# project_Sheet.net
KiCad netlist of a schematic drawn in Altium Designer
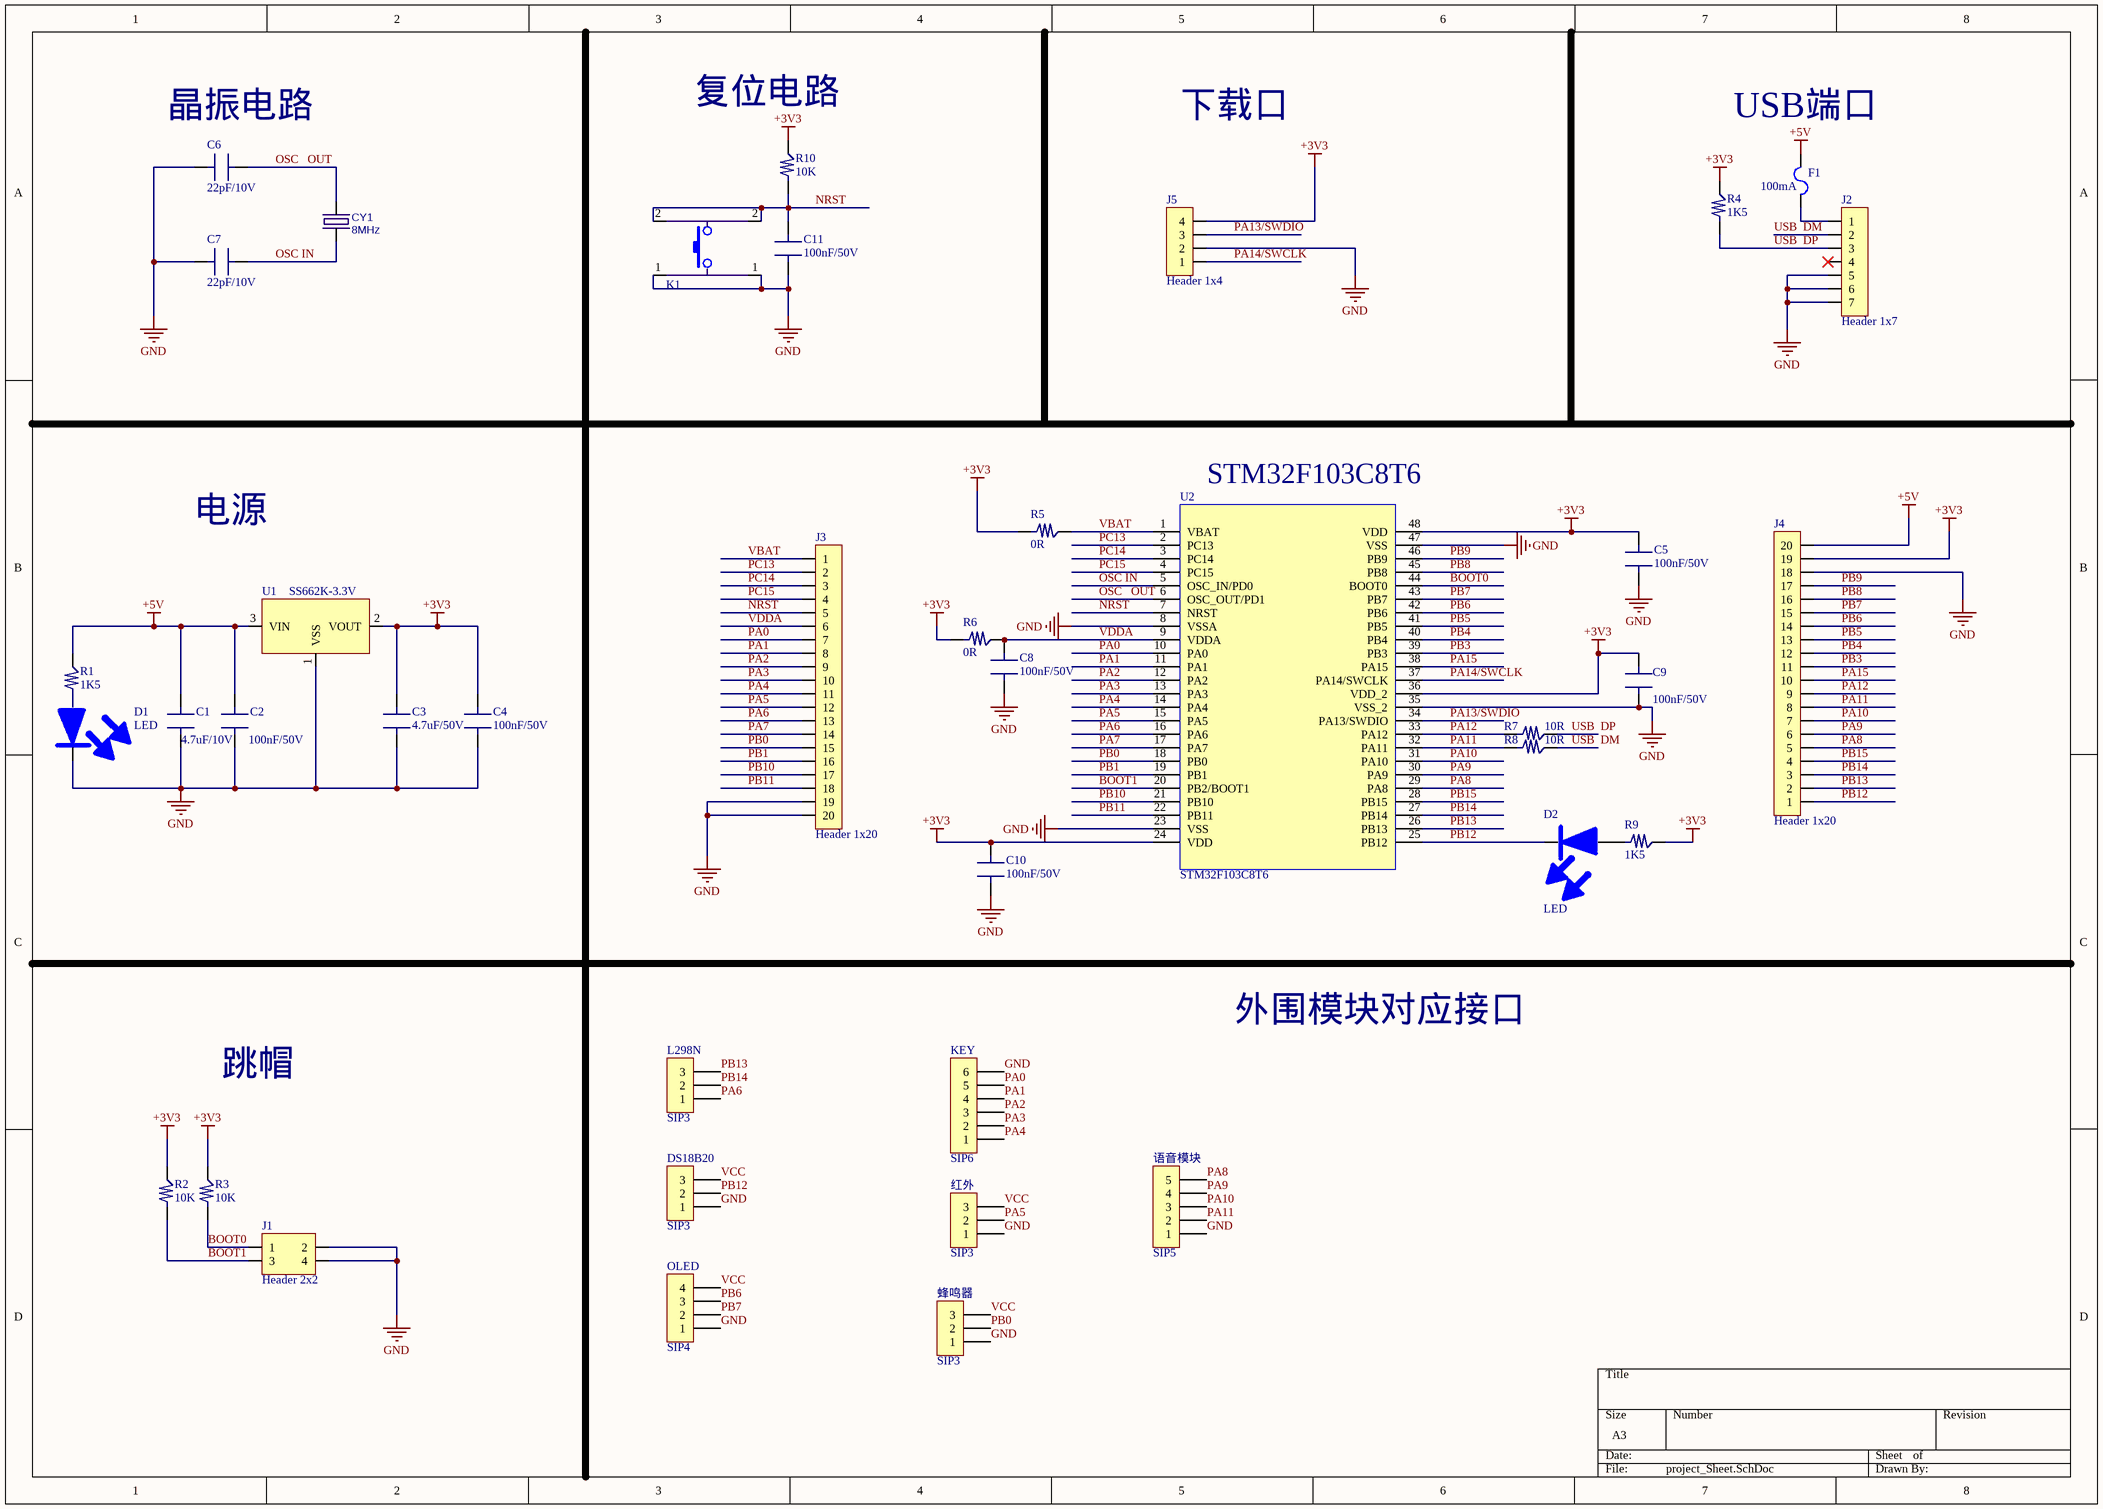
[diagram p0: project_Sheet.SchDoc]

(export (version "E")
  (design (tool "Eeschema 10.0.6"))
  (components
    (comp (ref "C1") (value "4.7uF/10V") (footprint "0603CC") (libsource (lib "F1A") (part "CAP")))
    (comp (ref "C2") (value "100nF/50V") (footprint "0603CC") (libsource (lib "F1A") (part "CAP")))
    (comp (ref "C3") (value "4.7uF/50V") (footprint "0805CC") (libsource (lib "F1A") (part "CAP")))
    (comp (ref "C4") (value "100nF/50V") (footprint "0805CC") (libsource (lib "F1A") (part "CAP")))
    (comp (ref "C5") (value "100nF/50V") (footprint "0603CC") (libsource (lib "F1A") (part "CAP")))
    (comp (ref "C6") (value "22pF/10V") (footprint "0603CC") (libsource (lib "F1A") (part "CAP")))
    (comp (ref "C7") (value "22pF/10V") (footprint "0603CC") (libsource (lib "F1A") (part "CAP")))
    (comp (ref "C8") (value "100nF/50V") (footprint "0603CC") (libsource (lib "F1A") (part "CAP")))
    (comp (ref "C9") (value "100nF/50V") (footprint "0603CC") (libsource (lib "F1A") (part "CAP")))
    (comp (ref "C10") (value "100nF/50V") (footprint "0603CC") (libsource (lib "F1A") (part "CAP")))
    (comp (ref "C11") (value "100nF/50V") (footprint "0603CC") (libsource (lib "F1A") (part "CAP")))
    (comp (ref "CY1")
      (value "8MHz")
      (footprint "HC-49S")
      (description "2pin晶振")
      (libsource (lib "F1A") (part "CY2P"))
    )
    (comp (ref "D1") (value "LED") (footprint "0603LED") (libsource (lib "F1A") (part "LED")))
    (comp (ref "D2") (value "LED") (footprint "0603LED") (libsource (lib "F1A") (part "LED")))
    (comp (ref "DS18B20")
      (value "SIP3")
      (footprint "SIP3-2.0")
      (description "jointbar")
      (libsource (lib "接口与插座") (part "SIP3"))
    )
    (comp (ref "F1")
      (value "100mA")
      (footprint "R0805")
      (description "保险丝")
      (libsource (lib "F1A") (part "FUSE"))
    )
    (comp (ref "J1")
      (value "Header 2x2")
      (footprint "HDR2X2")
      (description "双排连接器")
      (libsource (lib "F1A") (part "Header2*2"))
    )
    (comp (ref "J2")
      (value "Header 1x7")
      (footprint "PCBComponent_1")
      (description "单排连接器")
      (libsource (lib "F1A") (part "Header 1x7"))
    )
    (comp (ref "J3")
      (value "Header 1x20")
      (footprint "HDR1X20")
      (description "单排连接器")
      (libsource (lib "") (part "Header 1x20_1"))
    )
    (comp (ref "J4")
      (value "Header 1x20")
      (footprint "HDR1X20")
      (description "单排连接器")
      (libsource (lib "F1A") (part "Header 1x20"))
    )
    (comp (ref "J5")
      (value "Header 1x4")
      (footprint "HDR1X4")
      (description "单排连接器")
      (libsource (lib "F1A") (part "Header 1x4"))
    )
    (comp (ref "K1")
      (value "SW4P")
      (footprint "4.5*4.5*3.8")
      (description "4Pin轻触按键")
      (libsource (lib "F1A") (part "SW4P"))
    )
    (comp (ref "KEY")
      (value "SIP6")
      (footprint "SIP6-2.0")
      (description "jointbar")
      (libsource (lib "接口与插座") (part "SIP6"))
    )
    (comp (ref "L298N")
      (value "SIP3")
      (footprint "SIP3-2.0")
      (description "jointbar")
      (libsource (lib "接口与插座") (part "SIP3"))
    )
    (comp (ref "OLED")
      (value "SIP4")
      (footprint "SIP4-2.0")
      (description "jointbar")
      (libsource (lib "接口与插座") (part "SIP4"))
    )
    (comp (ref "R1")
      (value "1K5")
      (footprint "0603R")
      (description "分立电阻")
      (libsource (lib "F1A") (part "RES"))
    )
    (comp (ref "R2")
      (value "10K")
      (footprint "0603R")
      (description "分立电阻")
      (libsource (lib "F1A") (part "RES"))
    )
    (comp (ref "R3")
      (value "10K")
      (footprint "0603R")
      (description "分立电阻")
      (libsource (lib "F1A") (part "RES"))
    )
    (comp (ref "R4")
      (value "1K5")
      (footprint "0603R")
      (description "分立电阻")
      (libsource (lib "F1A") (part "RES"))
    )
    (comp (ref "R5")
      (value "0R")
      (footprint "0603R")
      (description "分立电阻")
      (libsource (lib "F1A") (part "RES"))
    )
    (comp (ref "R6")
      (value "0R")
      (footprint "0603R")
      (description "分立电阻")
      (libsource (lib "F1A") (part "RES"))
    )
    (comp (ref "R7")
      (value "10R")
      (footprint "0603R")
      (description "分立电阻")
      (libsource (lib "F1A") (part "RES"))
    )
    (comp (ref "R8")
      (value "10R")
      (footprint "0603R")
      (description "分立电阻")
      (libsource (lib "F1A") (part "RES"))
    )
    (comp (ref "R9")
      (value "1K5")
      (footprint "0603R")
      (description "分立电阻")
      (libsource (lib "F1A") (part "RES"))
    )
    (comp (ref "R10")
      (value "10K")
      (footprint "0603R")
      (description "分立电阻")
      (libsource (lib "F1A") (part "RES"))
    )
    (comp (ref "U1") (value "SS662K-3.3V") (footprint "SOT23-JX") (libsource (lib "F1A") (part "SS662K")))
    (comp (ref "U2")
      (value "STM32F103C8T6")
      (footprint "LQFP48")
      (description "STM32单片机")
      (libsource (lib "F1A") (part "STM32F103C8T6"))
    )
    (comp (ref "红外")
      (value "SIP3")
      (footprint "SIP3-2.0")
      (description "jointbar")
      (libsource (lib "接口与插座") (part "SIP3"))
    )
    (comp (ref "蜂鸣器")
      (value "SIP3")
      (footprint "SIP3-2.0")
      (description "jointbar")
      (libsource (lib "接口与插座") (part "SIP3"))
    )
    (comp (ref "语音模块")
      (value "SIP5")
      (footprint "SIP5-2.0")
      (description "jointbar")
      (libsource (lib "接口与插座") (part "SIP5"))
    )
  )
  (nets
    (net (code "1") (name "+3V3") (class "Default")
      (node (ref "C10") (pin "2") (pinfunction "2_2") (pintype "passive"))
      (node (ref "C3") (pin "2") (pinfunction "2_2") (pintype "passive"))
      (node (ref "C4") (pin "2") (pinfunction "2_2") (pintype "passive"))
      (node (ref "C5") (pin "2") (pinfunction "2_2") (pintype "passive"))
      (node (ref "C9") (pin "2") (pinfunction "2_2") (pintype "passive"))
      (node (ref "J4") (pin "19") (pinfunction "19_19") (pintype "passive"))
      (node (ref "J5") (pin "4") (pinfunction "4_4") (pintype "passive"))
      (node (ref "R10") (pin "2") (pinfunction "2_2") (pintype "passive"))
      (node (ref "R2") (pin "2") (pinfunction "2_2") (pintype "passive"))
      (node (ref "R3") (pin "2") (pinfunction "2_2") (pintype "passive"))
      (node (ref "R4") (pin "2") (pinfunction "2_2") (pintype "passive"))
      (node (ref "R5") (pin "1") (pinfunction "1_1") (pintype "passive"))
      (node (ref "R6") (pin "1") (pinfunction "1_1") (pintype "passive"))
      (node (ref "R9") (pin "2") (pinfunction "2_2") (pintype "passive"))
      (node (ref "U1") (pin "2") (pinfunction "VOUT_2") (pintype "passive"))
      (node (ref "U2") (pin "24") (pinfunction "VDD_24") (pintype "passive"))
      (node (ref "U2") (pin "36") (pinfunction "VDD_2_36") (pintype "passive"))
      (node (ref "U2") (pin "48") (pinfunction "VDD_48") (pintype "passive"))
    )
    (net (code "2") (name "+5V") (class "Default")
      (node (ref "C1") (pin "2") (pinfunction "2_2") (pintype "passive"))
      (node (ref "C2") (pin "2") (pinfunction "2_2") (pintype "passive"))
      (node (ref "F1") (pin "2") (pinfunction "2_2") (pintype "passive"))
      (node (ref "J4") (pin "20") (pinfunction "20_20") (pintype "passive"))
      (node (ref "R1") (pin "2") (pinfunction "2_2") (pintype "passive"))
      (node (ref "U1") (pin "3") (pinfunction "VIN_3") (pintype "passive"))
    )
    (net (code "3") (name "/BOOT0") (class "Default")
      (node (ref "J1") (pin "1") (pinfunction "1_1") (pintype "passive"))
      (node (ref "R3") (pin "1") (pinfunction "1_1") (pintype "passive"))
      (node (ref "U2") (pin "44") (pinfunction "BOOT0_44") (pintype "passive"))
    )
    (net (code "4") (name "/BOOT1") (class "Default")
      (node (ref "J1") (pin "3") (pinfunction "3_3") (pintype "passive"))
      (node (ref "R2") (pin "1") (pinfunction "1_1") (pintype "passive"))
      (node (ref "U2") (pin "20") (pinfunction "PB2/BOOT1_20") (pintype "passive"))
    )
    (net (code "5") (name "/NRST") (class "Default")
      (node (ref "C11") (pin "2") (pinfunction "2_2") (pintype "passive"))
      (node (ref "J3") (pin "5") (pinfunction "5_5") (pintype "passive"))
      (node (ref "K1") (pin "2") (pinfunction "3_2") (pintype "passive"))
      (node (ref "R10") (pin "1") (pinfunction "1_1") (pintype "passive"))
      (node (ref "U2") (pin "7") (pinfunction "NRST_7") (pintype "passive"))
    )
    (net (code "6") (name "/OSC   OUT") (class "Default")
      (node (ref "C6") (pin "2") (pinfunction "2_2") (pintype "passive"))
      (node (ref "CY1") (pin "2") (pinfunction "2_2") (pintype "passive"))
      (node (ref "U2") (pin "6") (pinfunction "OSC_OUT/PD1_6") (pintype "passive"))
    )
    (net (code "7") (name "/OSC IN") (class "Default")
      (node (ref "C7") (pin "2") (pinfunction "2_2") (pintype "passive"))
      (node (ref "CY1") (pin "1") (pinfunction "1_1") (pintype "passive"))
      (node (ref "U2") (pin "5") (pinfunction "OSC_IN/PD0_5") (pintype "passive"))
    )
    (net (code "8") (name "/PA0") (class "Default")
      (node (ref "J3") (pin "7") (pinfunction "7_7") (pintype "passive"))
      (node (ref "KEY") (pin "5") (pinfunction "5_5") (pintype "passive"))
      (node (ref "U2") (pin "10") (pinfunction "PA0_10") (pintype "passive"))
    )
    (net (code "9") (name "/PA1") (class "Default")
      (node (ref "J3") (pin "8") (pinfunction "8_8") (pintype "passive"))
      (node (ref "KEY") (pin "4") (pinfunction "4_4") (pintype "passive"))
      (node (ref "U2") (pin "11") (pinfunction "PA1_11") (pintype "passive"))
    )
    (net (code "10") (name "/PA2") (class "Default")
      (node (ref "J3") (pin "9") (pinfunction "9_9") (pintype "passive"))
      (node (ref "KEY") (pin "3") (pinfunction "3_3") (pintype "passive"))
      (node (ref "U2") (pin "12") (pinfunction "PA2_12") (pintype "passive"))
    )
    (net (code "11") (name "/PA3") (class "Default")
      (node (ref "J3") (pin "10") (pinfunction "10_10") (pintype "passive"))
      (node (ref "KEY") (pin "2") (pinfunction "2_2") (pintype "passive"))
      (node (ref "U2") (pin "13") (pinfunction "PA3_13") (pintype "passive"))
    )
    (net (code "12") (name "/PA4") (class "Default")
      (node (ref "J3") (pin "11") (pinfunction "11_11") (pintype "passive"))
      (node (ref "KEY") (pin "1") (pinfunction "1_1") (pintype "passive"))
      (node (ref "U2") (pin "14") (pinfunction "PA4_14") (pintype "passive"))
    )
    (net (code "13") (name "/PA5") (class "Default")
      (node (ref "J3") (pin "12") (pinfunction "12_12") (pintype "passive"))
      (node (ref "U2") (pin "15") (pinfunction "PA5_15") (pintype "passive"))
      (node (ref "红外") (pin "2") (pinfunction "2_2") (pintype "passive"))
    )
    (net (code "14") (name "/PA6") (class "Default")
      (node (ref "J3") (pin "13") (pinfunction "13_13") (pintype "passive"))
      (node (ref "L298N") (pin "1") (pinfunction "1_1") (pintype "passive"))
      (node (ref "U2") (pin "16") (pinfunction "PA6_16") (pintype "passive"))
    )
    (net (code "15") (name "/PA7") (class "Default")
      (node (ref "J3") (pin "14") (pinfunction "14_14") (pintype "passive"))
      (node (ref "U2") (pin "17") (pinfunction "PA7_17") (pintype "passive"))
    )
    (net (code "16") (name "/PA8") (class "Default")
      (node (ref "J4") (pin "5") (pinfunction "5_5") (pintype "passive"))
      (node (ref "U2") (pin "29") (pinfunction "PA8_29") (pintype "passive"))
      (node (ref "语音模块") (pin "5") (pinfunction "5_5") (pintype "passive"))
    )
    (net (code "17") (name "/PA9") (class "Default")
      (node (ref "J4") (pin "6") (pinfunction "6_6") (pintype "passive"))
      (node (ref "U2") (pin "30") (pinfunction "PA9_30") (pintype "passive"))
      (node (ref "语音模块") (pin "4") (pinfunction "4_4") (pintype "passive"))
    )
    (net (code "18") (name "/PA10") (class "Default")
      (node (ref "J4") (pin "7") (pinfunction "7_7") (pintype "passive"))
      (node (ref "U2") (pin "31") (pinfunction "PA10_31") (pintype "passive"))
      (node (ref "语音模块") (pin "3") (pinfunction "3_3") (pintype "passive"))
    )
    (net (code "19") (name "/PA11") (class "Default")
      (node (ref "J4") (pin "8") (pinfunction "8_8") (pintype "passive"))
      (node (ref "R8") (pin "1") (pinfunction "1_1") (pintype "passive"))
      (node (ref "U2") (pin "32") (pinfunction "PA11_32") (pintype "passive"))
      (node (ref "语音模块") (pin "2") (pinfunction "2_2") (pintype "passive"))
    )
    (net (code "20") (name "/PA12") (class "Default")
      (node (ref "J4") (pin "9") (pinfunction "9_9") (pintype "passive"))
      (node (ref "R7") (pin "1") (pinfunction "1_1") (pintype "passive"))
      (node (ref "U2") (pin "33") (pinfunction "PA12_33") (pintype "passive"))
    )
    (net (code "21") (name "/PA13{slash}SWDIO") (class "Default")
      (node (ref "J5") (pin "3") (pinfunction "3_3") (pintype "passive"))
      (node (ref "U2") (pin "34") (pinfunction "PA13/SWDIO_34") (pintype "passive"))
    )
    (net (code "22") (name "/PA14{slash}SWCLK") (class "Default")
      (node (ref "J5") (pin "1") (pinfunction "1_1") (pintype "passive"))
      (node (ref "U2") (pin "37") (pinfunction "PA14/SWCLK_37") (pintype "passive"))
    )
    (net (code "23") (name "/PA15") (class "Default")
      (node (ref "J4") (pin "10") (pinfunction "10_10") (pintype "passive"))
      (node (ref "U2") (pin "38") (pinfunction "PA15_38") (pintype "passive"))
    )
    (net (code "24") (name "/PB0") (class "Default")
      (node (ref "J3") (pin "15") (pinfunction "15_15") (pintype "passive"))
      (node (ref "U2") (pin "18") (pinfunction "PB0_18") (pintype "passive"))
      (node (ref "蜂鸣器") (pin "2") (pinfunction "2_2") (pintype "passive"))
    )
    (net (code "25") (name "/PB1") (class "Default")
      (node (ref "J3") (pin "16") (pinfunction "16_16") (pintype "passive"))
      (node (ref "U2") (pin "19") (pinfunction "PB1_19") (pintype "passive"))
    )
    (net (code "26") (name "/PB3") (class "Default")
      (node (ref "J4") (pin "11") (pinfunction "11_11") (pintype "passive"))
      (node (ref "U2") (pin "39") (pinfunction "PB3_39") (pintype "passive"))
    )
    (net (code "27") (name "/PB4") (class "Default")
      (node (ref "J4") (pin "12") (pinfunction "12_12") (pintype "passive"))
      (node (ref "U2") (pin "40") (pinfunction "PB4_40") (pintype "passive"))
    )
    (net (code "28") (name "/PB5") (class "Default")
      (node (ref "J4") (pin "13") (pinfunction "13_13") (pintype "passive"))
      (node (ref "U2") (pin "41") (pinfunction "PB5_41") (pintype "passive"))
    )
    (net (code "29") (name "/PB6") (class "Default")
      (node (ref "J4") (pin "14") (pinfunction "14_14") (pintype "passive"))
      (node (ref "OLED") (pin "3") (pinfunction "3_3") (pintype "passive"))
      (node (ref "U2") (pin "42") (pinfunction "PB6_42") (pintype "passive"))
    )
    (net (code "30") (name "/PB7") (class "Default")
      (node (ref "J4") (pin "15") (pinfunction "15_15") (pintype "passive"))
      (node (ref "OLED") (pin "2") (pinfunction "2_2") (pintype "passive"))
      (node (ref "U2") (pin "43") (pinfunction "PB7_43") (pintype "passive"))
    )
    (net (code "31") (name "/PB8") (class "Default")
      (node (ref "J4") (pin "16") (pinfunction "16_16") (pintype "passive"))
      (node (ref "U2") (pin "45") (pinfunction "PB8_45") (pintype "passive"))
    )
    (net (code "32") (name "/PB9") (class "Default")
      (node (ref "J4") (pin "17") (pinfunction "17_17") (pintype "passive"))
      (node (ref "U2") (pin "46") (pinfunction "PB9_46") (pintype "passive"))
    )
    (net (code "33") (name "/PB10") (class "Default")
      (node (ref "J3") (pin "17") (pinfunction "17_17") (pintype "passive"))
      (node (ref "U2") (pin "21") (pinfunction "PB10_21") (pintype "passive"))
    )
    (net (code "34") (name "/PB11") (class "Default")
      (node (ref "J3") (pin "18") (pinfunction "18_18") (pintype "passive"))
      (node (ref "U2") (pin "22") (pinfunction "PB11_22") (pintype "passive"))
    )
    (net (code "35") (name "/PB12") (class "Default")
      (node (ref "D2") (pin "2") (pinfunction "2_2") (pintype "passive"))
      (node (ref "DS18B20") (pin "2") (pinfunction "2_2") (pintype "passive"))
      (node (ref "J4") (pin "1") (pinfunction "1_1") (pintype "passive"))
      (node (ref "U2") (pin "25") (pinfunction "PB12_25") (pintype "passive"))
    )
    (net (code "36") (name "/PB13") (class "Default")
      (node (ref "J4") (pin "2") (pinfunction "2_2") (pintype "passive"))
      (node (ref "L298N") (pin "3") (pinfunction "3_3") (pintype "passive"))
      (node (ref "U2") (pin "26") (pinfunction "PB13_26") (pintype "passive"))
    )
    (net (code "37") (name "/PB14") (class "Default")
      (node (ref "J4") (pin "3") (pinfunction "3_3") (pintype "passive"))
      (node (ref "L298N") (pin "2") (pinfunction "2_2") (pintype "passive"))
      (node (ref "U2") (pin "27") (pinfunction "PB14_27") (pintype "passive"))
    )
    (net (code "38") (name "/PB15") (class "Default")
      (node (ref "J4") (pin "4") (pinfunction "4_4") (pintype "passive"))
      (node (ref "U2") (pin "28") (pinfunction "PB15_28") (pintype "passive"))
    )
    (net (code "39") (name "/PC13") (class "Default")
      (node (ref "J3") (pin "2") (pinfunction "2_2") (pintype "passive"))
      (node (ref "U2") (pin "2") (pinfunction "PC13_2") (pintype "passive"))
    )
    (net (code "40") (name "/PC14") (class "Default")
      (node (ref "J3") (pin "3") (pinfunction "3_3") (pintype "passive"))
      (node (ref "U2") (pin "3") (pinfunction "PC14_3") (pintype "passive"))
    )
    (net (code "41") (name "/PC15") (class "Default")
      (node (ref "J3") (pin "4") (pinfunction "4_4") (pintype "passive"))
      (node (ref "U2") (pin "4") (pinfunction "PC15_4") (pintype "passive"))
    )
    (net (code "42") (name "/USB  DM") (class "Default")
      (node (ref "J2") (pin "2") (pinfunction "2_2") (pintype "passive"))
      (node (ref "R8") (pin "2") (pinfunction "2_2") (pintype "passive"))
    )
    (net (code "43") (name "/USB  DP") (class "Default")
      (node (ref "J2") (pin "3") (pinfunction "3_3") (pintype "passive"))
      (node (ref "R4") (pin "1") (pinfunction "1_1") (pintype "passive"))
      (node (ref "R7") (pin "2") (pinfunction "2_2") (pintype "passive"))
    )
    (net (code "44") (name "/VBAT") (class "Default")
      (node (ref "J3") (pin "1") (pinfunction "1_1") (pintype "passive"))
      (node (ref "R5") (pin "2") (pinfunction "2_2") (pintype "passive"))
      (node (ref "U2") (pin "1") (pinfunction "VBAT_1") (pintype "passive"))
    )
    (net (code "45") (name "/VCC") (class "Default")
      (node (ref "DS18B20") (pin "3") (pinfunction "3_3") (pintype "passive"))
      (node (ref "OLED") (pin "4") (pinfunction "4_4") (pintype "passive"))
      (node (ref "红外") (pin "3") (pinfunction "3_3") (pintype "passive"))
      (node (ref "蜂鸣器") (pin "3") (pinfunction "3_3") (pintype "passive"))
    )
    (net (code "46") (name "/VDDA") (class "Default")
      (node (ref "C8") (pin "2") (pinfunction "2_2") (pintype "passive"))
      (node (ref "J3") (pin "6") (pinfunction "6_6") (pintype "passive"))
      (node (ref "R6") (pin "2") (pinfunction "2_2") (pintype "passive"))
      (node (ref "U2") (pin "9") (pinfunction "VDDA_9") (pintype "passive"))
    )
    (net (code "47") (name "GND") (class "Default")
      (node (ref "C1") (pin "1") (pinfunction "1_1") (pintype "passive"))
      (node (ref "C10") (pin "1") (pinfunction "1_1") (pintype "passive"))
      (node (ref "C11") (pin "1") (pinfunction "1_1") (pintype "passive"))
      (node (ref "C2") (pin "1") (pinfunction "1_1") (pintype "passive"))
      (node (ref "C3") (pin "1") (pinfunction "1_1") (pintype "passive"))
      (node (ref "C4") (pin "1") (pinfunction "1_1") (pintype "passive"))
      (node (ref "C5") (pin "1") (pinfunction "1_1") (pintype "passive"))
      (node (ref "C6") (pin "1") (pinfunction "1_1") (pintype "passive"))
      (node (ref "C7") (pin "1") (pinfunction "1_1") (pintype "passive"))
      (node (ref "C8") (pin "1") (pinfunction "1_1") (pintype "passive"))
      (node (ref "C9") (pin "1") (pinfunction "1_1") (pintype "passive"))
      (node (ref "D1") (pin "2") (pinfunction "2_2") (pintype "passive"))
      (node (ref "DS18B20") (pin "1") (pinfunction "1_1") (pintype "passive"))
      (node (ref "J1") (pin "2") (pinfunction "2_2") (pintype "passive"))
      (node (ref "J1") (pin "4") (pinfunction "4_4") (pintype "passive"))
      (node (ref "J2") (pin "5") (pinfunction "5_5") (pintype "passive"))
      (node (ref "J2") (pin "6") (pinfunction "6_6") (pintype "passive"))
      (node (ref "J2") (pin "7") (pinfunction "7_7") (pintype "passive"))
      (node (ref "J3") (pin "19") (pinfunction "19_19") (pintype "passive"))
      (node (ref "J3") (pin "20") (pinfunction "20_20") (pintype "passive"))
      (node (ref "J4") (pin "18") (pinfunction "18_18") (pintype "passive"))
      (node (ref "J5") (pin "2") (pinfunction "2_2") (pintype "passive"))
      (node (ref "K1") (pin "1") (pinfunction "2_1") (pintype "passive"))
      (node (ref "KEY") (pin "6") (pinfunction "6_6") (pintype "passive"))
      (node (ref "OLED") (pin "1") (pinfunction "1_1") (pintype "passive"))
      (node (ref "U1") (pin "1") (pinfunction "VSS_1") (pintype "passive"))
      (node (ref "U2") (pin "23") (pinfunction "VSS_23") (pintype "passive"))
      (node (ref "U2") (pin "35") (pinfunction "VSS_2_35") (pintype "passive"))
      (node (ref "U2") (pin "47") (pinfunction "VSS_47") (pintype "passive"))
      (node (ref "U2") (pin "8") (pinfunction "VSSA_8") (pintype "passive"))
      (node (ref "红外") (pin "1") (pinfunction "1_1") (pintype "passive"))
      (node (ref "蜂鸣器") (pin "1") (pinfunction "1_1") (pintype "passive"))
      (node (ref "语音模块") (pin "1") (pinfunction "1_1") (pintype "passive"))
    )
    (net (code "48") (name "Net-(D1-Pad1)") (class "Default")
      (node (ref "D1") (pin "1") (pinfunction "1_1") (pintype "passive"))
      (node (ref "R1") (pin "1") (pinfunction "1_1") (pintype "passive"))
    )
    (net (code "49") (name "Net-(D2-Pad1)") (class "Default")
      (node (ref "D2") (pin "1") (pinfunction "1_1") (pintype "passive"))
      (node (ref "R9") (pin "1") (pinfunction "1_1") (pintype "passive"))
    )
    (net (code "50") (name "Net-(F1-Pad1)") (class "Default")
      (node (ref "F1") (pin "1") (pinfunction "1_1") (pintype "passive"))
      (node (ref "J2") (pin "1") (pinfunction "1_1") (pintype "passive"))
    )
    (net (code "51") (name "unconnected-(J2-Pad4)") (class "Default")
      (node (ref "J2") (pin "4") (pinfunction "4_4") (pintype "passive+no_connect"))
    )
  )
)
